# PARduino.net
KiCad netlist of a schematic drawn in EAGLE
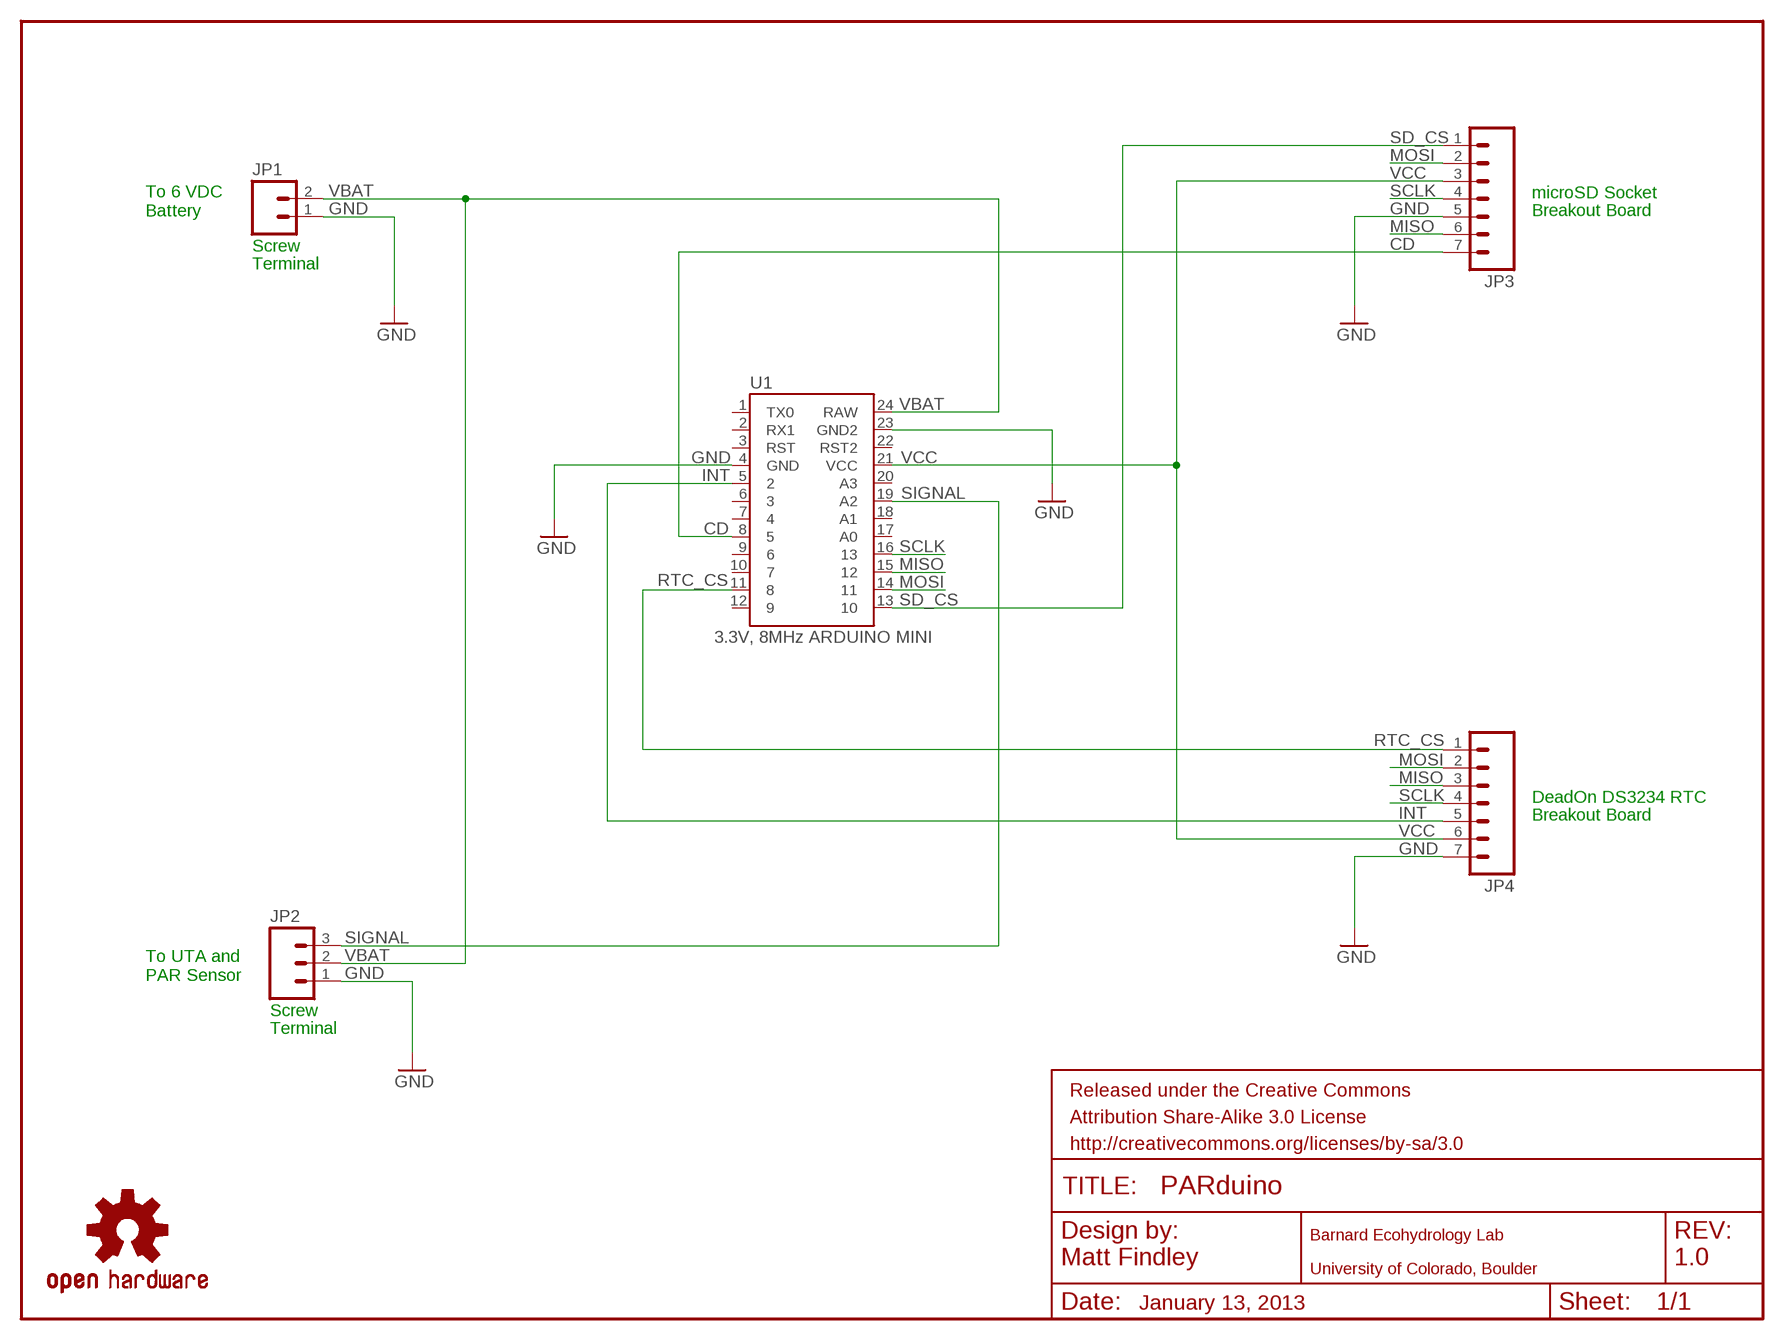
[diagram p0: schematic, sheet 1]

(export (version "E")
  (design (tool "Eeschema 10.0.6"))
  (components
    (comp (ref "JP1")
      (value "M023.5MM_LOCK")
      (footprint "eagle-import:SCREWTERMINAL-3.5MM-2_LOCK")
      (libsource (lib "eagle-import") (part "M023.5MM_LOCK"))
    )
    (comp (ref "JP2")
      (value "M03SCREW")
      (footprint "eagle-import:SCREWTERMINAL-3.5MM-3")
      (libsource (lib "eagle-import") (part "M03SCREW"))
    )
    (comp (ref "JP3")
      (value "M07LOCK")
      (footprint "eagle-import:1X07_LOCK")
      (libsource (lib "eagle-import") (part "M07LOCK"))
    )
    (comp (ref "JP4")
      (value "M07LOCK")
      (footprint "eagle-import:1X07_LOCK")
      (libsource (lib "eagle-import") (part "M07LOCK"))
    )
    (comp (ref "LOGO")
      (value "OSHW-LOGOL")
      (footprint "eagle-import:OSHW-LOGO-L")
      (libsource (lib "eagle-import") (part "OSHW-LOGOL"))
    )
    (comp (ref "U1")
      (value "3.3V, 8MHz ARDUINO MINI")
      (footprint "eagle-import:ARDUINO_MINI")
      (libsource (lib "eagle-import") (part "ARDUINO_MINI"))
    )
  )
  (nets
    (net (code "1") (name "/CD") (class "Default")
      (node (ref "JP3") (pin "7") (pinfunction "7_7") (pintype "passive"))
      (node (ref "U1") (pin "8") (pinfunction "5_8") (pintype "bidirectional"))
    )
    (net (code "2") (name "/INT") (class "Default")
      (node (ref "JP4") (pin "5") (pinfunction "5_5") (pintype "passive"))
      (node (ref "U1") (pin "5") (pinfunction "2_5") (pintype "bidirectional"))
    )
    (net (code "3") (name "/MISO") (class "Default")
      (node (ref "JP3") (pin "6") (pinfunction "6_6") (pintype "passive"))
      (node (ref "JP4") (pin "3") (pinfunction "3_3") (pintype "passive"))
      (node (ref "U1") (pin "15") (pinfunction "12_15") (pintype "bidirectional"))
    )
    (net (code "4") (name "/MOSI") (class "Default")
      (node (ref "JP3") (pin "2") (pinfunction "2_2") (pintype "passive"))
      (node (ref "JP4") (pin "2") (pinfunction "2_2") (pintype "passive"))
      (node (ref "U1") (pin "14") (pinfunction "11_14") (pintype "bidirectional"))
    )
    (net (code "5") (name "/RTC_CS") (class "Default")
      (node (ref "JP4") (pin "1") (pinfunction "1_1") (pintype "passive"))
      (node (ref "U1") (pin "11") (pinfunction "8_11") (pintype "bidirectional"))
    )
    (net (code "6") (name "/SCLK") (class "Default")
      (node (ref "JP3") (pin "4") (pinfunction "4_4") (pintype "passive"))
      (node (ref "JP4") (pin "4") (pinfunction "4_4") (pintype "passive"))
      (node (ref "U1") (pin "16") (pinfunction "13_16") (pintype "bidirectional"))
    )
    (net (code "7") (name "/SD_CS") (class "Default")
      (node (ref "JP3") (pin "1") (pinfunction "1_1") (pintype "passive"))
      (node (ref "U1") (pin "13") (pinfunction "10_13") (pintype "bidirectional"))
    )
    (net (code "8") (name "/SIGNAL") (class "Default")
      (node (ref "JP2") (pin "3") (pinfunction "3_3") (pintype "passive"))
      (node (ref "U1") (pin "19") (pinfunction "A2_19") (pintype "bidirectional"))
    )
    (net (code "9") (name "/VBAT") (class "Default")
      (node (ref "JP1") (pin "2") (pinfunction "2_2") (pintype "passive"))
      (node (ref "JP2") (pin "2") (pinfunction "2_2") (pintype "passive"))
      (node (ref "U1") (pin "24") (pinfunction "RAW_24") (pintype "bidirectional"))
    )
    (net (code "10") (name "/VCC") (class "Default")
      (node (ref "JP3") (pin "3") (pinfunction "3_3") (pintype "passive"))
      (node (ref "JP4") (pin "6") (pinfunction "6_6") (pintype "passive"))
      (node (ref "U1") (pin "21") (pinfunction "VCC_21") (pintype "bidirectional"))
    )
    (net (code "11") (name "GND") (class "Default")
      (node (ref "JP1") (pin "1") (pinfunction "1_1") (pintype "passive"))
      (node (ref "JP2") (pin "1") (pinfunction "1_1") (pintype "passive"))
      (node (ref "JP3") (pin "5") (pinfunction "5_5") (pintype "passive"))
      (node (ref "JP4") (pin "7") (pinfunction "7_7") (pintype "passive"))
      (node (ref "U1") (pin "23") (pinfunction "GND2_23") (pintype "bidirectional"))
      (node (ref "U1") (pin "4") (pinfunction "GND_4") (pintype "bidirectional"))
    )
    (net (code "12") (name "unconnected-(U1-3-Pad6)") (class "Default")
      (node (ref "U1") (pin "6") (pinfunction "3_6") (pintype "bidirectional"))
    )
    (net (code "13") (name "unconnected-(U1-4-Pad7)") (class "Default")
      (node (ref "U1") (pin "7") (pinfunction "4_7") (pintype "bidirectional"))
    )
    (net (code "14") (name "unconnected-(U1-6-Pad9)") (class "Default")
      (node (ref "U1") (pin "9") (pinfunction "6_9") (pintype "bidirectional"))
    )
    (net (code "15") (name "unconnected-(U1-7-Pad10)") (class "Default")
      (node (ref "U1") (pin "10") (pinfunction "7_10") (pintype "bidirectional"))
    )
    (net (code "16") (name "unconnected-(U1-9-Pad12)") (class "Default")
      (node (ref "U1") (pin "12") (pinfunction "9_12") (pintype "bidirectional"))
    )
    (net (code "17") (name "unconnected-(U1-A0-Pad17)") (class "Default")
      (node (ref "U1") (pin "17") (pinfunction "A0_17") (pintype "bidirectional"))
    )
    (net (code "18") (name "unconnected-(U1-A1-Pad18)") (class "Default")
      (node (ref "U1") (pin "18") (pinfunction "A1_18") (pintype "bidirectional"))
    )
    (net (code "19") (name "unconnected-(U1-A3-Pad20)") (class "Default")
      (node (ref "U1") (pin "20") (pinfunction "A3_20") (pintype "bidirectional"))
    )
    (net (code "20") (name "unconnected-(U1-RST-Pad3)") (class "Default")
      (node (ref "U1") (pin "3") (pinfunction "RST_3") (pintype "bidirectional"))
    )
    (net (code "21") (name "unconnected-(U1-RST2-Pad22)") (class "Default")
      (node (ref "U1") (pin "22") (pinfunction "RST2_22") (pintype "bidirectional"))
    )
    (net (code "22") (name "unconnected-(U1-RX1-Pad2)") (class "Default")
      (node (ref "U1") (pin "2") (pinfunction "RX1_2") (pintype "bidirectional"))
    )
    (net (code "23") (name "unconnected-(U1-TX0-Pad1)") (class "Default")
      (node (ref "U1") (pin "1") (pinfunction "TX0_1") (pintype "bidirectional"))
    )
  )
)
